# Engine.net
KiCad netlist of a schematic drawn in Altium Designer
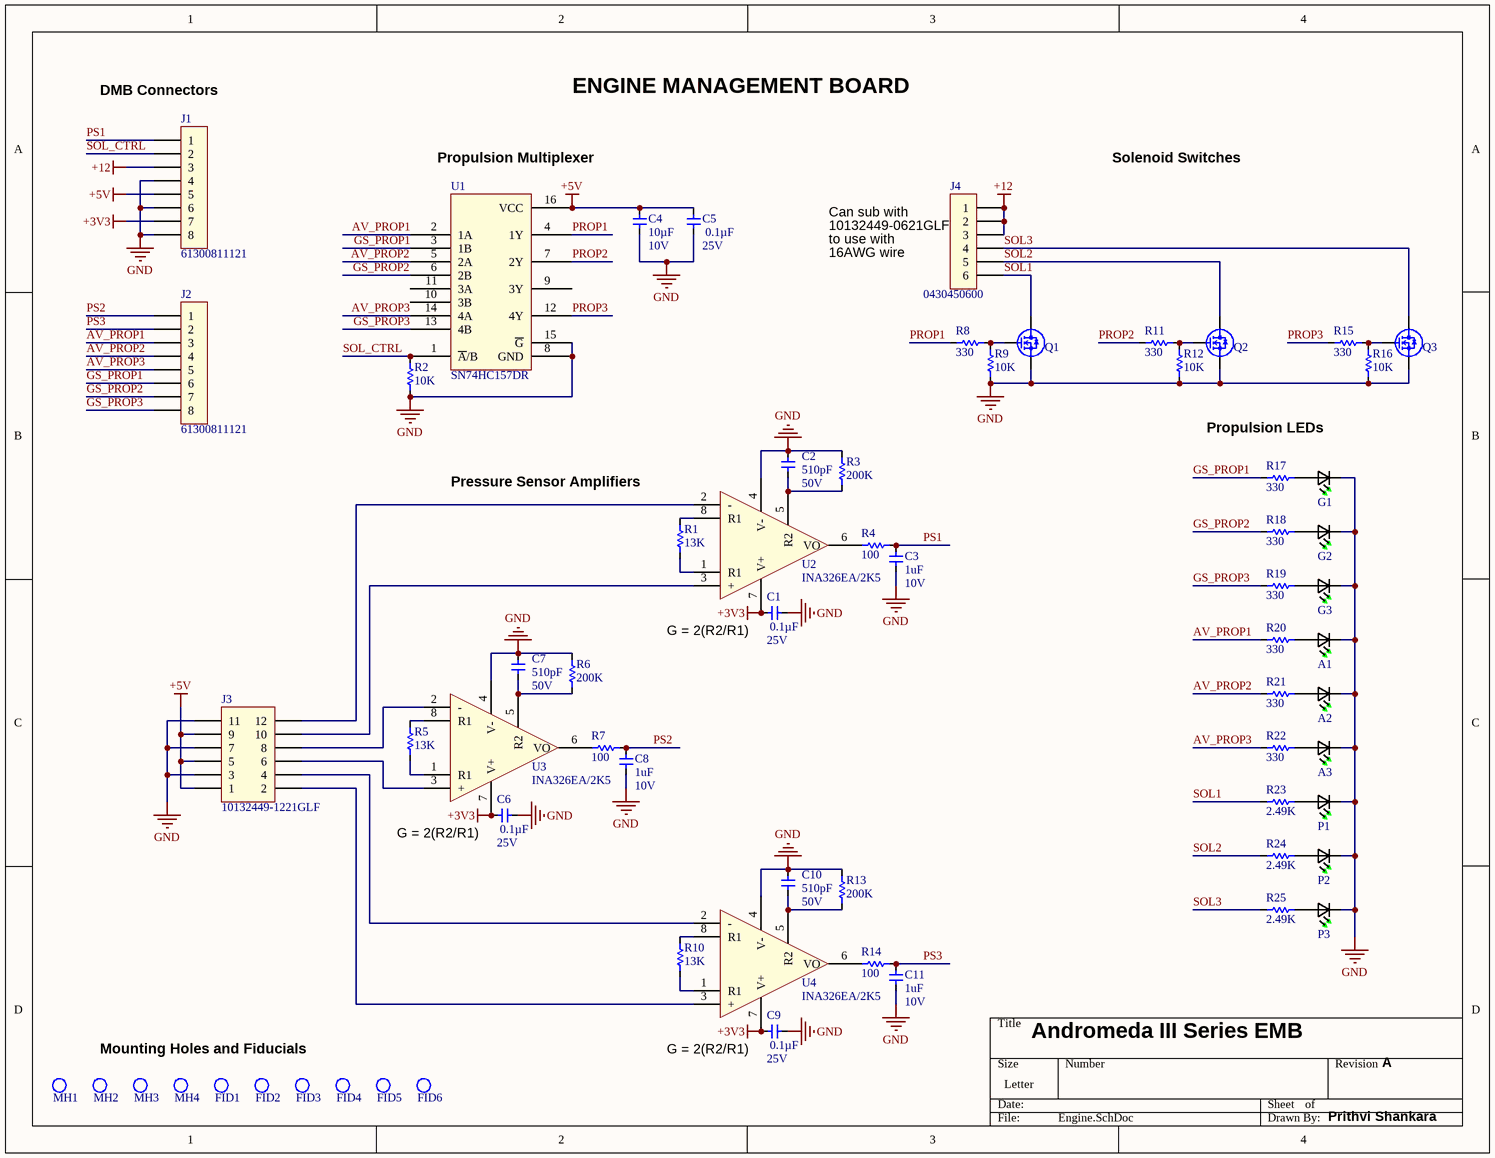
[diagram p0: Engine.SchDoc]

(export (version "E")
  (design (tool "Eeschema 10.0.6"))
  (components
    (comp (ref "A1")
      (value "LTST-C191KGKT")
      (footprint "LTST-C191KGKT")
      (description "LED GREEN CLEAR SMD 0603")
      (fields (field (name "MANUFACTURER") "Lite-On Inc."))
      (libsource (lib "SOARSchematics") (part "LTST-C191KGKT"))
    )
    (comp (ref "A2")
      (value "LTST-C191KGKT")
      (footprint "LTST-C191KGKT")
      (description "LED GREEN CLEAR SMD 0603")
      (fields (field (name "MANUFACTURER") "Lite-On Inc."))
      (libsource (lib "SOARSchematics") (part "LTST-C191KGKT"))
    )
    (comp (ref "A3")
      (value "LTST-C191KGKT")
      (footprint "LTST-C191KGKT")
      (description "LED GREEN CLEAR SMD 0603")
      (fields (field (name "MANUFACTURER") "Lite-On Inc."))
      (libsource (lib "SOARSchematics") (part "LTST-C191KGKT"))
    )
    (comp (ref "C1")
      (value "CGA3E2X7R1E104K080AA")
      (footprint "0603[1608]")
      (description "CAP CER 0.1UF 25V X7R 0603")
      (fields
        (field (name "MANUFACTURER") "TDK Corporation")
        (field (name "TOLERANCE") "±10%")
        (field (name "CAPACITANCE") " 0.1µF")
        (field (name "VOLTAGE - RATED") "25V")
      )
      (libsource (lib "SOARSchematics") (part "CGA3E2X7R1E104K080AA"))
    )
    (comp (ref "C2")
      (value "CC0603JRNPO9BN511")
      (footprint "0603[1608]")
      (description "CAP CER 4.7UF 25V X5R 0603")
      (fields
        (field (name "MANUFACTURER") "Yageo")
        (field (name "TOLERANCE") "±5%")
        (field (name "CAPACITANCE") "510pF")
        (field (name "VOLTAGE - RATED") "50V")
      )
      (libsource (lib "SOARSchematics") (part "CC0603JRNPO9BN511"))
    )
    (comp (ref "C3")
      (value "CL10A105KP8NNNC")
      (footprint "0603[1608]")
      (description "CAP CER 1UF 10V X5R 0603")
      (fields
        (field (name "MANUFACTURER") "Samsung Electro-Mechanics")
        (field (name "TOLERANCE") "±10%")
        (field (name "CAPACITANCE") "1uF")
        (field (name "VOLTAGE - RATED") "10V")
      )
      (libsource (lib "SOARSchematics") (part "CL10A105KP8NNNC"))
    )
    (comp (ref "C4")
      (value "CL10A106MP8NNNC")
      (footprint "0603[1608]")
      (description "CAP CER 10UF 10V X5R 0603")
      (fields
        (field (name "MANUFACTURER") "Samsung Electro-Mechanics")
        (field (name "TOLERANCE") "±20%")
        (field (name "CAPACITANCE") "10µF")
        (field (name "VOLTAGE - RATED") "10V")
      )
      (libsource (lib "SOARSchematics") (part "CL10A106MP8NNNC"))
    )
    (comp (ref "C5")
      (value "CGA3E2X7R1E104K080AA")
      (footprint "0603[1608]")
      (description "CAP CER 0.1UF 25V X7R 0603")
      (fields
        (field (name "MANUFACTURER") "TDK Corporation")
        (field (name "TOLERANCE") "±10%")
        (field (name "CAPACITANCE") " 0.1µF")
        (field (name "VOLTAGE - RATED") "25V")
      )
      (libsource (lib "SOARSchematics") (part "CGA3E2X7R1E104K080AA"))
    )
    (comp (ref "C6")
      (value "CGA3E2X7R1E104K080AA")
      (footprint "0603[1608]")
      (description "CAP CER 0.1UF 25V X7R 0603")
      (fields
        (field (name "MANUFACTURER") "TDK Corporation")
        (field (name "TOLERANCE") "±10%")
        (field (name "CAPACITANCE") " 0.1µF")
        (field (name "VOLTAGE - RATED") "25V")
      )
      (libsource (lib "SOARSchematics") (part "CGA3E2X7R1E104K080AA"))
    )
    (comp (ref "C7")
      (value "CC0603JRNPO9BN511")
      (footprint "0603[1608]")
      (description "CAP CER 4.7UF 25V X5R 0603")
      (fields
        (field (name "MANUFACTURER") "Yageo")
        (field (name "TOLERANCE") "±5%")
        (field (name "CAPACITANCE") "510pF")
        (field (name "VOLTAGE - RATED") "50V")
      )
      (libsource (lib "SOARSchematics") (part "CC0603JRNPO9BN511"))
    )
    (comp (ref "C8")
      (value "CL10A105KP8NNNC")
      (footprint "0603[1608]")
      (description "CAP CER 1UF 10V X5R 0603")
      (fields
        (field (name "MANUFACTURER") "Samsung Electro-Mechanics")
        (field (name "TOLERANCE") "±10%")
        (field (name "CAPACITANCE") "1uF")
        (field (name "VOLTAGE - RATED") "10V")
      )
      (libsource (lib "SOARSchematics") (part "CL10A105KP8NNNC"))
    )
    (comp (ref "C9")
      (value "CGA3E2X7R1E104K080AA")
      (footprint "0603[1608]")
      (description "CAP CER 0.1UF 25V X7R 0603")
      (fields
        (field (name "MANUFACTURER") "TDK Corporation")
        (field (name "TOLERANCE") "±10%")
        (field (name "CAPACITANCE") " 0.1µF")
        (field (name "VOLTAGE - RATED") "25V")
      )
      (libsource (lib "SOARSchematics") (part "CGA3E2X7R1E104K080AA"))
    )
    (comp (ref "C10")
      (value "CC0603JRNPO9BN511")
      (footprint "0603[1608]")
      (description "CAP CER 4.7UF 25V X5R 0603")
      (fields
        (field (name "MANUFACTURER") "Yageo")
        (field (name "TOLERANCE") "±5%")
        (field (name "CAPACITANCE") "510pF")
        (field (name "VOLTAGE - RATED") "50V")
      )
      (libsource (lib "SOARSchematics") (part "CC0603JRNPO9BN511"))
    )
    (comp (ref "C11")
      (value "CL10A105KP8NNNC")
      (footprint "0603[1608]")
      (description "CAP CER 1UF 10V X5R 0603")
      (fields
        (field (name "MANUFACTURER") "Samsung Electro-Mechanics")
        (field (name "TOLERANCE") "±10%")
        (field (name "CAPACITANCE") "1uF")
        (field (name "VOLTAGE - RATED") "10V")
      )
      (libsource (lib "SOARSchematics") (part "CL10A105KP8NNNC"))
    )
    (comp (ref "FID1")
      (value "FID_1MM_ROUND_SL")
      (footprint "FID_1MM_ROUND_SL")
      (description "Fiducial 1mm Round Single Layer")
      (libsource (lib "SOARSchematics") (part "FID_1MM_ROUND_SL"))
    )
    (comp (ref "FID2")
      (value "FID_1MM_ROUND_SL")
      (footprint "FID_1MM_ROUND_SL")
      (description "Fiducial 1mm Round Single Layer")
      (libsource (lib "SOARSchematics") (part "FID_1MM_ROUND_SL"))
    )
    (comp (ref "FID3")
      (value "FID_1MM_ROUND_SL")
      (footprint "FID_1MM_ROUND_SL")
      (description "Fiducial 1mm Round Single Layer")
      (libsource (lib "SOARSchematics") (part "FID_1MM_ROUND_SL"))
    )
    (comp (ref "FID4")
      (value "FID_1MM_ROUND_SL")
      (footprint "FID_1MM_ROUND_SL")
      (description "Fiducial 1mm Round Single Layer")
      (libsource (lib "SOARSchematics") (part "FID_1MM_ROUND_SL"))
    )
    (comp (ref "FID5")
      (value "FID_1MM_ROUND_SL")
      (footprint "FID_1MM_ROUND_SL")
      (description "Fiducial 1mm Round Single Layer")
      (libsource (lib "SOARSchematics") (part "FID_1MM_ROUND_SL"))
    )
    (comp (ref "FID6")
      (value "FID_1MM_ROUND_SL")
      (footprint "FID_1MM_ROUND_SL")
      (description "Fiducial 1mm Round Single Layer")
      (libsource (lib "SOARSchematics") (part "FID_1MM_ROUND_SL"))
    )
    (comp (ref "G1")
      (value "LTST-C191KGKT")
      (footprint "LTST-C191KGKT")
      (description "LED GREEN CLEAR SMD 0603")
      (fields (field (name "MANUFACTURER") "Lite-On Inc."))
      (libsource (lib "SOARSchematics") (part "LTST-C191KGKT"))
    )
    (comp (ref "G2")
      (value "LTST-C191KGKT")
      (footprint "LTST-C191KGKT")
      (description "LED GREEN CLEAR SMD 0603")
      (fields (field (name "MANUFACTURER") "Lite-On Inc."))
      (libsource (lib "SOARSchematics") (part "LTST-C191KGKT"))
    )
    (comp (ref "G3")
      (value "LTST-C191KGKT")
      (footprint "LTST-C191KGKT")
      (description "LED GREEN CLEAR SMD 0603")
      (fields (field (name "MANUFACTURER") "Lite-On Inc."))
      (libsource (lib "SOARSchematics") (part "LTST-C191KGKT"))
    )
    (comp (ref "J1")
      (value "61300811121")
      (footprint "61300811121")
      (description "CONN HEADER VERT 8POS  MALE 2.54MM")
      (fields (field (name "MANUFACTURER") "Würth Elektronik"))
      (libsource (lib "SOARSchematics") (part "61300811121"))
    )
    (comp (ref "J2")
      (value "61300811121")
      (footprint "61300811121")
      (description "CONN HEADER VERT 8POS  MALE 2.54MM")
      (fields (field (name "MANUFACTURER") "Würth Elektronik"))
      (libsource (lib "SOARSchematics") (part "61300811121"))
    )
    (comp (ref "J3")
      (value "10132449-1221GLF")
      (footprint "10132449-1221GLF")
      (description "CONN HEADER R/A 12POS 3MM")
      (fields (field (name "MANUFACTURER") "Amphenol ICC (FCI)"))
      (libsource (lib "SOARSchematics") (part "10132449-1221GLF"))
    )
    (comp (ref "J4")
      (value "0430450600")
      (footprint "0430450600")
      (description "CONN HEADER R/A 6POS 3MM")
      (fields (field (name "MANUFACTURER") "Molex"))
      (libsource (lib "SOARSchematics") (part "0430450600"))
    )
    (comp (ref "MH1")
      (value "9774110360R")
      (footprint "Standoff")
      (description "ROUND STANDOFF M3X0.5 STEEL 11MM")
      (fields (field (name "MANUFACTURER") "Würth Elektronik"))
      (libsource (lib "SOARSchematics") (part "9774110360R"))
    )
    (comp (ref "MH2")
      (value "9774110360R")
      (footprint "Standoff")
      (description "ROUND STANDOFF M3X0.5 STEEL 11MM")
      (fields (field (name "MANUFACTURER") "Würth Elektronik"))
      (libsource (lib "SOARSchematics") (part "9774110360R"))
    )
    (comp (ref "MH3")
      (value "Mounting Hole")
      (footprint "MOUNT-HOLE")
      (description "#4 Screw, 0.116in Diameter")
      (libsource (lib "SOARSchematics") (part "Mounting Hole"))
    )
    (comp (ref "MH4")
      (value "Mounting Hole")
      (footprint "MOUNT-HOLE")
      (description "#4 Screw, 0.116in Diameter")
      (libsource (lib "SOARSchematics") (part "Mounting Hole"))
    )
    (comp (ref "P1")
      (value "LTST-C191KGKT")
      (footprint "LTST-C191KGKT")
      (description "LED GREEN CLEAR SMD 0603")
      (fields (field (name "MANUFACTURER") "Lite-On Inc."))
      (libsource (lib "SOARSchematics") (part "LTST-C191KGKT"))
    )
    (comp (ref "P2")
      (value "LTST-C191KGKT")
      (footprint "LTST-C191KGKT")
      (description "LED GREEN CLEAR SMD 0603")
      (fields (field (name "MANUFACTURER") "Lite-On Inc."))
      (libsource (lib "SOARSchematics") (part "LTST-C191KGKT"))
    )
    (comp (ref "P3")
      (value "LTST-C191KGKT")
      (footprint "LTST-C191KGKT")
      (description "LED GREEN CLEAR SMD 0603")
      (fields (field (name "MANUFACTURER") "Lite-On Inc."))
      (libsource (lib "SOARSchematics") (part "LTST-C191KGKT"))
    )
    (comp (ref "Q1")
      (value "DMN3023L-7")
      (footprint "DMN3023L-7")
      (description "MOSFET N-CH 30V 6.2A SOT23")
      (fields (field (name "MANUFACTURER") "Diodes Incorporated"))
      (libsource (lib "SOARSchematics") (part "DMN3023L-7"))
    )
    (comp (ref "Q2")
      (value "DMN3023L-7")
      (footprint "DMN3023L-7")
      (description "MOSFET N-CH 30V 6.2A SOT23")
      (fields (field (name "MANUFACTURER") "Diodes Incorporated"))
      (libsource (lib "SOARSchematics") (part "DMN3023L-7"))
    )
    (comp (ref "Q3")
      (value "DMN3023L-7")
      (footprint "DMN3023L-7")
      (description "MOSFET N-CH 30V 6.2A SOT23")
      (fields (field (name "MANUFACTURER") "Diodes Incorporated"))
      (libsource (lib "SOARSchematics") (part "DMN3023L-7"))
    )
    (comp (ref "R1")
      (value "MCT06030C1302FP500")
      (footprint "0603[1608]")
      (description "RES SMD 13K OHM 1% 1/8W 0603")
      (fields
        (field (name "MANUFACTURER") "Vishay Beyschlag")
        (field (name "TOLERANCE") "±1%")
        (field (name "RESISTANCE") "13K")
      )
      (libsource (lib "SOARSchematics") (part "MCT06030C1302FP500"))
    )
    (comp (ref "R2")
      (value "ERJ-3GEYJ103V")
      (footprint "0603[1608]")
      (description "RES SMD 10K OHM 5% 1/10W 0603")
      (fields
        (field (name "TOLERANCE") "±5%")
        (field (name "MANUFACTURER") "Panasonic Electronic Components")
        (field (name "RESISTANCE") "10K")
      )
      (libsource (lib "SOARSchematics") (part "ERJ-3GEYJ103V"))
    )
    (comp (ref "R3")
      (value "ERJ-3EKF2003V")
      (footprint "0603[1608]")
      (description "RES SMD 200K OHM 1% 1/10W 0603")
      (fields
        (field (name "TOLERANCE") "±1%")
        (field (name "MANUFACTURER") "Panasonic Electronic Components")
        (field (name "RESISTANCE") "200K")
      )
      (libsource (lib "SOARSchematics") (part "ERJ-3EKF2003V"))
    )
    (comp (ref "R4")
      (value "ESR03EZPJ101")
      (footprint "0603[1608]")
      (description "RES SMD 100 OHM 5% 1/4W 0603")
      (fields
        (field (name "TOLERANCE") "±5%")
        (field (name "MANUFACTURER") "Rohm Semiconductor")
        (field (name "RESISTANCE") "100")
      )
      (libsource (lib "SOARSchematics") (part "ESR03EZPJ101"))
    )
    (comp (ref "R5")
      (value "MCT06030C1302FP500")
      (footprint "0603[1608]")
      (description "RES SMD 13K OHM 1% 1/8W 0603")
      (fields
        (field (name "MANUFACTURER") "Vishay Beyschlag")
        (field (name "TOLERANCE") "±1%")
        (field (name "RESISTANCE") "13K")
      )
      (libsource (lib "SOARSchematics") (part "MCT06030C1302FP500"))
    )
    (comp (ref "R6")
      (value "ERJ-3EKF2003V")
      (footprint "0603[1608]")
      (description "RES SMD 200K OHM 1% 1/10W 0603")
      (fields
        (field (name "TOLERANCE") "±1%")
        (field (name "MANUFACTURER") "Panasonic Electronic Components")
        (field (name "RESISTANCE") "200K")
      )
      (libsource (lib "SOARSchematics") (part "ERJ-3EKF2003V"))
    )
    (comp (ref "R7")
      (value "ESR03EZPJ101")
      (footprint "0603[1608]")
      (description "RES SMD 100 OHM 5% 1/4W 0603")
      (fields
        (field (name "TOLERANCE") "±5%")
        (field (name "MANUFACTURER") "Rohm Semiconductor")
        (field (name "RESISTANCE") "100")
      )
      (libsource (lib "SOARSchematics") (part "ESR03EZPJ101"))
    )
    (comp (ref "R8")
      (value "RC1608F331CS")
      (footprint "0603[1608]")
      (description "RES SMD 330 OHM 1% 1/10W 0603")
      (fields
        (field (name "TOLERANCE") "±1%")
        (field (name "MANUFACTURER") "Samsung Electro-Mechanics")
        (field (name "RESISTANCE") "330")
      )
      (libsource (lib "SOARSchematics") (part "RC1608F331CS"))
    )
    (comp (ref "R9")
      (value "ERJ-3GEYJ103V")
      (footprint "0603[1608]")
      (description "RES SMD 10K OHM 5% 1/10W 0603")
      (fields
        (field (name "TOLERANCE") "±5%")
        (field (name "MANUFACTURER") "Panasonic Electronic Components")
        (field (name "RESISTANCE") "10K")
      )
      (libsource (lib "SOARSchematics") (part "ERJ-3GEYJ103V"))
    )
    (comp (ref "R10")
      (value "MCT06030C1302FP500")
      (footprint "0603[1608]")
      (description "RES SMD 13K OHM 1% 1/8W 0603")
      (fields
        (field (name "MANUFACTURER") "Vishay Beyschlag")
        (field (name "TOLERANCE") "±1%")
        (field (name "RESISTANCE") "13K")
      )
      (libsource (lib "SOARSchematics") (part "MCT06030C1302FP500"))
    )
    (comp (ref "R11")
      (value "RC1608F331CS")
      (footprint "0603[1608]")
      (description "RES SMD 330 OHM 1% 1/10W 0603")
      (fields
        (field (name "TOLERANCE") "±1%")
        (field (name "MANUFACTURER") "Samsung Electro-Mechanics")
        (field (name "RESISTANCE") "330")
      )
      (libsource (lib "SOARSchematics") (part "RC1608F331CS"))
    )
    (comp (ref "R12")
      (value "ERJ-3GEYJ103V")
      (footprint "0603[1608]")
      (description "RES SMD 10K OHM 5% 1/10W 0603")
      (fields
        (field (name "TOLERANCE") "±5%")
        (field (name "MANUFACTURER") "Panasonic Electronic Components")
        (field (name "RESISTANCE") "10K")
      )
      (libsource (lib "SOARSchematics") (part "ERJ-3GEYJ103V"))
    )
    (comp (ref "R13")
      (value "ERJ-3EKF2003V")
      (footprint "0603[1608]")
      (description "RES SMD 200K OHM 1% 1/10W 0603")
      (fields
        (field (name "TOLERANCE") "±1%")
        (field (name "MANUFACTURER") "Panasonic Electronic Components")
        (field (name "RESISTANCE") "200K")
      )
      (libsource (lib "SOARSchematics") (part "ERJ-3EKF2003V"))
    )
    (comp (ref "R14")
      (value "ESR03EZPJ101")
      (footprint "0603[1608]")
      (description "RES SMD 100 OHM 5% 1/4W 0603")
      (fields
        (field (name "TOLERANCE") "±5%")
        (field (name "MANUFACTURER") "Rohm Semiconductor")
        (field (name "RESISTANCE") "100")
      )
      (libsource (lib "SOARSchematics") (part "ESR03EZPJ101"))
    )
    (comp (ref "R15")
      (value "RC1608F331CS")
      (footprint "0603[1608]")
      (description "RES SMD 330 OHM 1% 1/10W 0603")
      (fields
        (field (name "TOLERANCE") "±1%")
        (field (name "MANUFACTURER") "Samsung Electro-Mechanics")
        (field (name "RESISTANCE") "330")
      )
      (libsource (lib "SOARSchematics") (part "RC1608F331CS"))
    )
    (comp (ref "R16")
      (value "ERJ-3GEYJ103V")
      (footprint "0603[1608]")
      (description "RES SMD 10K OHM 5% 1/10W 0603")
      (fields
        (field (name "TOLERANCE") "±5%")
        (field (name "MANUFACTURER") "Panasonic Electronic Components")
        (field (name "RESISTANCE") "10K")
      )
      (libsource (lib "SOARSchematics") (part "ERJ-3GEYJ103V"))
    )
    (comp (ref "R17")
      (value "RC1608F331CS")
      (footprint "0603[1608]")
      (description "RES SMD 330 OHM 1% 1/10W 0603")
      (fields
        (field (name "TOLERANCE") "±1%")
        (field (name "MANUFACTURER") "Samsung Electro-Mechanics")
        (field (name "RESISTANCE") "330")
      )
      (libsource (lib "SOARSchematics") (part "RC1608F331CS"))
    )
    (comp (ref "R18")
      (value "RC1608F331CS")
      (footprint "0603[1608]")
      (description "RES SMD 330 OHM 1% 1/10W 0603")
      (fields
        (field (name "TOLERANCE") "±1%")
        (field (name "MANUFACTURER") "Samsung Electro-Mechanics")
        (field (name "RESISTANCE") "330")
      )
      (libsource (lib "SOARSchematics") (part "RC1608F331CS"))
    )
    (comp (ref "R19")
      (value "RC1608F331CS")
      (footprint "0603[1608]")
      (description "RES SMD 330 OHM 1% 1/10W 0603")
      (fields
        (field (name "TOLERANCE") "±1%")
        (field (name "MANUFACTURER") "Samsung Electro-Mechanics")
        (field (name "RESISTANCE") "330")
      )
      (libsource (lib "SOARSchematics") (part "RC1608F331CS"))
    )
    (comp (ref "R20")
      (value "RC1608F331CS")
      (footprint "0603[1608]")
      (description "RES SMD 330 OHM 1% 1/10W 0603")
      (fields
        (field (name "TOLERANCE") "±1%")
        (field (name "MANUFACTURER") "Samsung Electro-Mechanics")
        (field (name "RESISTANCE") "330")
      )
      (libsource (lib "SOARSchematics") (part "RC1608F331CS"))
    )
    (comp (ref "R21")
      (value "RC1608F331CS")
      (footprint "0603[1608]")
      (description "RES SMD 330 OHM 1% 1/10W 0603")
      (fields
        (field (name "TOLERANCE") "±1%")
        (field (name "MANUFACTURER") "Samsung Electro-Mechanics")
        (field (name "RESISTANCE") "330")
      )
      (libsource (lib "SOARSchematics") (part "RC1608F331CS"))
    )
    (comp (ref "R22")
      (value "RC1608F331CS")
      (footprint "0603[1608]")
      (description "RES SMD 330 OHM 1% 1/10W 0603")
      (fields
        (field (name "TOLERANCE") "±1%")
        (field (name "MANUFACTURER") "Samsung Electro-Mechanics")
        (field (name "RESISTANCE") "330")
      )
      (libsource (lib "SOARSchematics") (part "RC1608F331CS"))
    )
    (comp (ref "R23")
      (value "ERA-3AEB2491V")
      (footprint "0603[1608]")
      (description "RES SMD 2.49KOHM 0.1% 1/10W 0603")
      (fields
        (field (name "TOLERANCE") "±0.1%")
        (field (name "MANUFACTURER") "Panasonic Electronic Components")
        (field (name "RESISTANCE") "2.49K")
      )
      (libsource (lib "SOARSchematics") (part "ERA-3AEB2491V"))
    )
    (comp (ref "R24")
      (value "ERA-3AEB2491V")
      (footprint "0603[1608]")
      (description "RES SMD 2.49KOHM 0.1% 1/10W 0603")
      (fields
        (field (name "TOLERANCE") "±0.1%")
        (field (name "MANUFACTURER") "Panasonic Electronic Components")
        (field (name "RESISTANCE") "2.49K")
      )
      (libsource (lib "SOARSchematics") (part "ERA-3AEB2491V"))
    )
    (comp (ref "R25")
      (value "ERA-3AEB2491V")
      (footprint "0603[1608]")
      (description "RES SMD 2.49KOHM 0.1% 1/10W 0603")
      (fields
        (field (name "TOLERANCE") "±0.1%")
        (field (name "MANUFACTURER") "Panasonic Electronic Components")
        (field (name "RESISTANCE") "2.49K")
      )
      (libsource (lib "SOARSchematics") (part "ERA-3AEB2491V"))
    )
    (comp (ref "U1")
      (value "SN74HC157DR")
      (footprint "SOIC127P600X175-16N")
      (description "IC QUAD 2-1LN DATASEL/MUX 16SOIC")
      (fields (field (name "MANUFACTURER") "Texas Instruments") (field (name "BASE PART NUMBER") "74HC157"))
      (libsource (lib "SOARSchematics") (part "SN74HC157DR"))
    )
    (comp (ref "U2")
      (value "INA326EA/2K5")
      (footprint "TSOP65P490X110-8N")
      (description "IC INST AMP 1 CIRCUIT 8VSSOP")
      (fields (field (name "BASE PART NUMBER") "INA326") (field (name "MANUFACTURER") "Texas Instruments"))
      (libsource (lib "SOARSchematics") (part "INA326EA/2K5"))
    )
    (comp (ref "U3")
      (value "INA326EA/2K5")
      (footprint "TSOP65P490X110-8N")
      (description "IC INST AMP 1 CIRCUIT 8VSSOP")
      (fields (field (name "BASE PART NUMBER") "INA326") (field (name "MANUFACTURER") "Texas Instruments"))
      (libsource (lib "SOARSchematics") (part "INA326EA/2K5"))
    )
    (comp (ref "U4")
      (value "INA326EA/2K5")
      (footprint "TSOP65P490X110-8N")
      (description "IC INST AMP 1 CIRCUIT 8VSSOP")
      (fields (field (name "BASE PART NUMBER") "INA326") (field (name "MANUFACTURER") "Texas Instruments"))
      (libsource (lib "SOARSchematics") (part "INA326EA/2K5"))
    )
  )
  (nets
    (net (code "1") (name "+3V3") (class "Default")
      (node (ref "C1") (pin "2") (pinfunction "2_2") (pintype "passive"))
      (node (ref "C6") (pin "2") (pinfunction "2_2") (pintype "passive"))
      (node (ref "C9") (pin "2") (pinfunction "2_2") (pintype "passive"))
      (node (ref "J1") (pin "7") (pinfunction "7_7") (pintype "passive"))
      (node (ref "U2") (pin "7") (pinfunction "V+_7") (pintype "power_in"))
      (node (ref "U3") (pin "7") (pinfunction "V+_7") (pintype "power_in"))
      (node (ref "U4") (pin "7") (pinfunction "V+_7") (pintype "power_in"))
    )
    (net (code "2") (name "+5V") (class "Default")
      (node (ref "C4") (pin "2") (pinfunction "2_2") (pintype "passive"))
      (node (ref "C5") (pin "2") (pinfunction "2_2") (pintype "passive"))
      (node (ref "J1") (pin "5") (pinfunction "5_5") (pintype "passive"))
      (node (ref "J3") (pin "1") (pinfunction "1_1") (pintype "passive"))
      (node (ref "J3") (pin "5") (pinfunction "5_5") (pintype "passive"))
      (node (ref "J3") (pin "9") (pinfunction "9_9") (pintype "passive"))
      (node (ref "U1") (pin "16") (pinfunction "VCC_16") (pintype "passive"))
    )
    (net (code "3") (name "+12") (class "Default")
      (node (ref "J1") (pin "3") (pinfunction "3_3") (pintype "passive"))
      (node (ref "J4") (pin "1") (pinfunction "1_1") (pintype "passive"))
      (node (ref "J4") (pin "2") (pinfunction "2_2") (pintype "passive"))
      (node (ref "J4") (pin "3") (pinfunction "3_3") (pintype "passive"))
    )
    (net (code "4") (name "/AV_PROP1") (class "Default")
      (node (ref "J2") (pin "3") (pinfunction "3_3") (pintype "passive"))
      (node (ref "R20") (pin "2") (pinfunction "2_2") (pintype "passive"))
      (node (ref "U1") (pin "2") (pinfunction "1A_2") (pintype "passive"))
    )
    (net (code "5") (name "/AV_PROP2") (class "Default")
      (node (ref "J2") (pin "4") (pinfunction "4_4") (pintype "passive"))
      (node (ref "R21") (pin "2") (pinfunction "2_2") (pintype "passive"))
      (node (ref "U1") (pin "5") (pinfunction "2A_5") (pintype "passive"))
    )
    (net (code "6") (name "/AV_PROP3") (class "Default")
      (node (ref "J2") (pin "5") (pinfunction "5_5") (pintype "passive"))
      (node (ref "R22") (pin "2") (pinfunction "2_2") (pintype "passive"))
      (node (ref "U1") (pin "14") (pinfunction "4A_14") (pintype "passive"))
    )
    (net (code "7") (name "/GS_PROP1") (class "Default")
      (node (ref "J2") (pin "6") (pinfunction "6_6") (pintype "passive"))
      (node (ref "R17") (pin "2") (pinfunction "2_2") (pintype "passive"))
      (node (ref "U1") (pin "3") (pinfunction "1B_3") (pintype "passive"))
    )
    (net (code "8") (name "/GS_PROP2") (class "Default")
      (node (ref "J2") (pin "7") (pinfunction "7_7") (pintype "passive"))
      (node (ref "R18") (pin "2") (pinfunction "2_2") (pintype "passive"))
      (node (ref "U1") (pin "6") (pinfunction "2B_6") (pintype "passive"))
    )
    (net (code "9") (name "/GS_PROP3") (class "Default")
      (node (ref "J2") (pin "8") (pinfunction "8_8") (pintype "passive"))
      (node (ref "R19") (pin "2") (pinfunction "2_2") (pintype "passive"))
      (node (ref "U1") (pin "13") (pinfunction "4B_13") (pintype "passive"))
    )
    (net (code "10") (name "/PROP1") (class "Default")
      (node (ref "R8") (pin "1") (pinfunction "1_1") (pintype "passive"))
      (node (ref "U1") (pin "4") (pinfunction "1Y_4") (pintype "passive"))
    )
    (net (code "11") (name "/PROP2") (class "Default")
      (node (ref "R11") (pin "1") (pinfunction "1_1") (pintype "passive"))
      (node (ref "U1") (pin "7") (pinfunction "2Y_7") (pintype "passive"))
    )
    (net (code "12") (name "/PROP3") (class "Default")
      (node (ref "R15") (pin "1") (pinfunction "1_1") (pintype "passive"))
      (node (ref "U1") (pin "12") (pinfunction "4Y_12") (pintype "passive"))
    )
    (net (code "13") (name "/PS1") (class "Default")
      (node (ref "C3") (pin "2") (pinfunction "2_2") (pintype "passive"))
      (node (ref "J1") (pin "1") (pinfunction "1_1") (pintype "passive"))
      (node (ref "R4") (pin "2") (pinfunction "2_2") (pintype "passive"))
    )
    (net (code "14") (name "/PS2") (class "Default")
      (node (ref "C8") (pin "2") (pinfunction "2_2") (pintype "passive"))
      (node (ref "J2") (pin "1") (pinfunction "1_1") (pintype "passive"))
      (node (ref "R7") (pin "2") (pinfunction "2_2") (pintype "passive"))
    )
    (net (code "15") (name "/PS3") (class "Default")
      (node (ref "C11") (pin "2") (pinfunction "2_2") (pintype "passive"))
      (node (ref "J2") (pin "2") (pinfunction "2_2") (pintype "passive"))
      (node (ref "R14") (pin "2") (pinfunction "2_2") (pintype "passive"))
    )
    (net (code "16") (name "/SOL1") (class "Default")
      (node (ref "J4") (pin "6") (pinfunction "6_6") (pintype "passive"))
      (node (ref "Q1") (pin "3") (pinfunction "D_3") (pintype "passive"))
      (node (ref "R23") (pin "2") (pinfunction "2_2") (pintype "passive"))
    )
    (net (code "17") (name "/SOL2") (class "Default")
      (node (ref "J4") (pin "5") (pinfunction "5_5") (pintype "passive"))
      (node (ref "Q2") (pin "3") (pinfunction "D_3") (pintype "passive"))
      (node (ref "R24") (pin "2") (pinfunction "2_2") (pintype "passive"))
    )
    (net (code "18") (name "/SOL3") (class "Default")
      (node (ref "J4") (pin "4") (pinfunction "4_4") (pintype "passive"))
      (node (ref "Q3") (pin "3") (pinfunction "D_3") (pintype "passive"))
      (node (ref "R25") (pin "2") (pinfunction "2_2") (pintype "passive"))
    )
    (net (code "19") (name "/SOL_CTRL") (class "Default")
      (node (ref "J1") (pin "2") (pinfunction "2_2") (pintype "passive"))
      (node (ref "R2") (pin "2") (pinfunction "2_2") (pintype "passive"))
      (node (ref "U1") (pin "1") (pinfunction "~{A}/B_1") (pintype "passive"))
    )
    (net (code "20") (name "GND") (class "Default")
      (node (ref "A1") (pin "1") (pinfunction "K2_1") (pintype "passive"))
      (node (ref "A2") (pin "1") (pinfunction "K2_1") (pintype "passive"))
      (node (ref "A3") (pin "1") (pinfunction "K2_1") (pintype "passive"))
      (node (ref "C1") (pin "1") (pinfunction "1_1") (pintype "passive"))
      (node (ref "C10") (pin "1") (pinfunction "1_1") (pintype "passive"))
      (node (ref "C11") (pin "1") (pinfunction "1_1") (pintype "passive"))
      (node (ref "C2") (pin "1") (pinfunction "1_1") (pintype "passive"))
      (node (ref "C3") (pin "1") (pinfunction "1_1") (pintype "passive"))
      (node (ref "C4") (pin "1") (pinfunction "1_1") (pintype "passive"))
      (node (ref "C5") (pin "1") (pinfunction "1_1") (pintype "passive"))
      (node (ref "C6") (pin "1") (pinfunction "1_1") (pintype "passive"))
      (node (ref "C7") (pin "1") (pinfunction "1_1") (pintype "passive"))
      (node (ref "C8") (pin "1") (pinfunction "1_1") (pintype "passive"))
      (node (ref "C9") (pin "1") (pinfunction "1_1") (pintype "passive"))
      (node (ref "G1") (pin "1") (pinfunction "K2_1") (pintype "passive"))
      (node (ref "G2") (pin "1") (pinfunction "K2_1") (pintype "passive"))
      (node (ref "G3") (pin "1") (pinfunction "K2_1") (pintype "passive"))
      (node (ref "J1") (pin "4") (pinfunction "4_4") (pintype "passive"))
      (node (ref "J1") (pin "6") (pinfunction "6_6") (pintype "passive"))
      (node (ref "J1") (pin "8") (pinfunction "8_8") (pintype "passive"))
      (node (ref "J3") (pin "11") (pinfunction "11_11") (pintype "passive"))
      (node (ref "J3") (pin "3") (pinfunction "3_3") (pintype "passive"))
      (node (ref "J3") (pin "7") (pinfunction "7_7") (pintype "passive"))
      (node (ref "P1") (pin "1") (pinfunction "K2_1") (pintype "passive"))
      (node (ref "P2") (pin "1") (pinfunction "K2_1") (pintype "passive"))
      (node (ref "P3") (pin "1") (pinfunction "K2_1") (pintype "passive"))
      (node (ref "Q1") (pin "2") (pinfunction "S_2") (pintype "passive"))
      (node (ref "Q2") (pin "2") (pinfunction "S_2") (pintype "passive"))
      (node (ref "Q3") (pin "2") (pinfunction "S_2") (pintype "passive"))
      (node (ref "R12") (pin "1") (pinfunction "1_1") (pintype "passive"))
      (node (ref "R13") (pin "1") (pinfunction "1_1") (pintype "passive"))
      (node (ref "R16") (pin "1") (pinfunction "1_1") (pintype "passive"))
      (node (ref "R2") (pin "1") (pinfunction "1_1") (pintype "passive"))
      (node (ref "R3") (pin "1") (pinfunction "1_1") (pintype "passive"))
      (node (ref "R6") (pin "1") (pinfunction "1_1") (pintype "passive"))
      (node (ref "R9") (pin "1") (pinfunction "1_1") (pintype "passive"))
      (node (ref "U1") (pin "15") (pinfunction "~{G}_15") (pintype "passive"))
      (node (ref "U1") (pin "8") (pinfunction "GND_8") (pintype "passive"))
      (node (ref "U2") (pin "4") (pinfunction "V-_4") (pintype "power_in"))
      (node (ref "U3") (pin "4") (pinfunction "V-_4") (pintype "power_in"))
      (node (ref "U4") (pin "4") (pinfunction "V-_4") (pintype "power_in"))
    )
    (net (code "21") (name "Net-(A1-A2)") (class "Default")
      (node (ref "A1") (pin "2") (pinfunction "A2_2") (pintype "passive"))
      (node (ref "R20") (pin "1") (pinfunction "1_1") (pintype "passive"))
    )
    (net (code "22") (name "Net-(A2-A2)") (class "Default")
      (node (ref "A2") (pin "2") (pinfunction "A2_2") (pintype "passive"))
      (node (ref "R21") (pin "1") (pinfunction "1_1") (pintype "passive"))
    )
    (net (code "23") (name "Net-(A3-A2)") (class "Default")
      (node (ref "A3") (pin "2") (pinfunction "A2_2") (pintype "passive"))
      (node (ref "R22") (pin "1") (pinfunction "1_1") (pintype "passive"))
    )
    (net (code "24") (name "Net-(G1-A2)") (class "Default")
      (node (ref "G1") (pin "2") (pinfunction "A2_2") (pintype "passive"))
      (node (ref "R17") (pin "1") (pinfunction "1_1") (pintype "passive"))
    )
    (net (code "25") (name "Net-(G2-A2)") (class "Default")
      (node (ref "G2") (pin "2") (pinfunction "A2_2") (pintype "passive"))
      (node (ref "R18") (pin "1") (pinfunction "1_1") (pintype "passive"))
    )
    (net (code "26") (name "Net-(G3-A2)") (class "Default")
      (node (ref "G3") (pin "2") (pinfunction "A2_2") (pintype "passive"))
      (node (ref "R19") (pin "1") (pinfunction "1_1") (pintype "passive"))
    )
    (net (code "27") (name "Net-(P1-A2)") (class "Default")
      (node (ref "P1") (pin "2") (pinfunction "A2_2") (pintype "passive"))
      (node (ref "R23") (pin "1") (pinfunction "1_1") (pintype "passive"))
    )
    (net (code "28") (name "Net-(P2-A2)") (class "Default")
      (node (ref "P2") (pin "2") (pinfunction "A2_2") (pintype "passive"))
      (node (ref "R24") (pin "1") (pinfunction "1_1") (pintype "passive"))
    )
    (net (code "29") (name "Net-(P3-A2)") (class "Default")
      (node (ref "P3") (pin "2") (pinfunction "A2_2") (pintype "passive"))
      (node (ref "R25") (pin "1") (pinfunction "1_1") (pintype "passive"))
    )
    (net (code "30") (name "Net-(Q1-G)") (class "Default")
      (node (ref "Q1") (pin "1") (pinfunction "G_1") (pintype "passive"))
      (node (ref "R8") (pin "2") (pinfunction "2_2") (pintype "passive"))
      (node (ref "R9") (pin "2") (pinfunction "2_2") (pintype "passive"))
    )
    (net (code "31") (name "Net-(Q2-G)") (class "Default")
      (node (ref "Q2") (pin "1") (pinfunction "G_1") (pintype "passive"))
      (node (ref "R11") (pin "2") (pinfunction "2_2") (pintype "passive"))
      (node (ref "R12") (pin "2") (pinfunction "2_2") (pintype "passive"))
    )
    (net (code "32") (name "Net-(Q3-G)") (class "Default")
      (node (ref "Q3") (pin "1") (pinfunction "G_1") (pintype "passive"))
      (node (ref "R15") (pin "2") (pinfunction "2_2") (pintype "passive"))
      (node (ref "R16") (pin "2") (pinfunction "2_2") (pintype "passive"))
    )
    (net (code "33") (name "Net-(R1-Pad1)") (class "Default")
      (node (ref "R1") (pin "1") (pinfunction "1_1") (pintype "passive"))
      (node (ref "U2") (pin "8") (pinfunction "R1_8") (pintype "passive"))
    )
    (net (code "34") (name "Net-(R1-Pad2)") (class "Default")
      (node (ref "R1") (pin "2") (pinfunction "2_2") (pintype "passive"))
      (node (ref "U2") (pin "1") (pinfunction "R1_1") (pintype "passive"))
    )
    (net (code "35") (name "Net-(R5-Pad1)") (class "Default")
      (node (ref "R5") (pin "1") (pinfunction "1_1") (pintype "passive"))
      (node (ref "U3") (pin "8") (pinfunction "R1_8") (pintype "passive"))
    )
    (net (code "36") (name "Net-(R5-Pad2)") (class "Default")
      (node (ref "R5") (pin "2") (pinfunction "2_2") (pintype "passive"))
      (node (ref "U3") (pin "1") (pinfunction "R1_1") (pintype "passive"))
    )
    (net (code "37") (name "Net-(R10-Pad1)") (class "Default")
      (node (ref "R10") (pin "1") (pinfunction "1_1") (pintype "passive"))
      (node (ref "U4") (pin "8") (pinfunction "R1_8") (pintype "passive"))
    )
    (net (code "38") (name "Net-(R10-Pad2)") (class "Default")
      (node (ref "R10") (pin "2") (pinfunction "2_2") (pintype "passive"))
      (node (ref "U4") (pin "1") (pinfunction "R1_1") (pintype "passive"))
    )
    (net (code "39") (name "Net-(U2-+)") (class "Default")
      (node (ref "J3") (pin "10") (pinfunction "10_10") (pintype "passive"))
      (node (ref "U2") (pin "3") (pinfunction "+_3") (pintype "passive"))
    )
    (net (code "40") (name "Net-(U2--)") (class "Default")
      (node (ref "J3") (pin "12") (pinfunction "12_12") (pintype "passive"))
      (node (ref "U2") (pin "2") (pinfunction "-_2") (pintype "passive"))
    )
    (net (code "41") (name "Net-(U2-R2)") (class "Default")
      (node (ref "C2") (pin "2") (pinfunction "2_2") (pintype "passive"))
      (node (ref "R3") (pin "2") (pinfunction "2_2") (pintype "passive"))
      (node (ref "U2") (pin "5") (pinfunction "R2_5") (pintype "passive"))
    )
    (net (code "42") (name "Net-(U2-VO)") (class "Default")
      (node (ref "R4") (pin "1") (pinfunction "1_1") (pintype "passive"))
      (node (ref "U2") (pin "6") (pinfunction "VO_6") (pintype "passive"))
    )
    (net (code "43") (name "Net-(U3-+)") (class "Default")
      (node (ref "J3") (pin "6") (pinfunction "6_6") (pintype "passive"))
      (node (ref "U3") (pin "3") (pinfunction "+_3") (pintype "passive"))
    )
    (net (code "44") (name "Net-(U3--)") (class "Default")
      (node (ref "J3") (pin "8") (pinfunction "8_8") (pintype "passive"))
      (node (ref "U3") (pin "2") (pinfunction "-_2") (pintype "passive"))
    )
    (net (code "45") (name "Net-(U3-R2)") (class "Default")
      (node (ref "C7") (pin "2") (pinfunction "2_2") (pintype "passive"))
      (node (ref "R6") (pin "2") (pinfunction "2_2") (pintype "passive"))
      (node (ref "U3") (pin "5") (pinfunction "R2_5") (pintype "passive"))
    )
    (net (code "46") (name "Net-(U3-VO)") (class "Default")
      (node (ref "R7") (pin "1") (pinfunction "1_1") (pintype "passive"))
      (node (ref "U3") (pin "6") (pinfunction "VO_6") (pintype "passive"))
    )
    (net (code "47") (name "Net-(U4-+)") (class "Default")
      (node (ref "J3") (pin "2") (pinfunction "2_2") (pintype "passive"))
      (node (ref "U4") (pin "3") (pinfunction "+_3") (pintype "passive"))
    )
    (net (code "48") (name "Net-(U4--)") (class "Default")
      (node (ref "J3") (pin "4") (pinfunction "4_4") (pintype "passive"))
      (node (ref "U4") (pin "2") (pinfunction "-_2") (pintype "passive"))
    )
    (net (code "49") (name "Net-(U4-R2)") (class "Default")
      (node (ref "C10") (pin "2") (pinfunction "2_2") (pintype "passive"))
      (node (ref "R13") (pin "2") (pinfunction "2_2") (pintype "passive"))
      (node (ref "U4") (pin "5") (pinfunction "R2_5") (pintype "passive"))
    )
    (net (code "50") (name "Net-(U4-VO)") (class "Default")
      (node (ref "R14") (pin "1") (pinfunction "1_1") (pintype "passive"))
      (node (ref "U4") (pin "6") (pinfunction "VO_6") (pintype "passive"))
    )
    (net (code "51") (name "unconnected-(U1-3A-Pad11)") (class "Default")
      (node (ref "U1") (pin "11") (pinfunction "3A_11") (pintype "passive"))
    )
    (net (code "52") (name "unconnected-(U1-3B-Pad10)") (class "Default")
      (node (ref "U1") (pin "10") (pinfunction "3B_10") (pintype "passive"))
    )
    (net (code "53") (name "unconnected-(U1-3Y-Pad9)") (class "Default")
      (node (ref "U1") (pin "9") (pinfunction "3Y_9") (pintype "passive"))
    )
  )
)
